# FrontendA.net
KiCad netlist of a schematic drawn in EAGLE
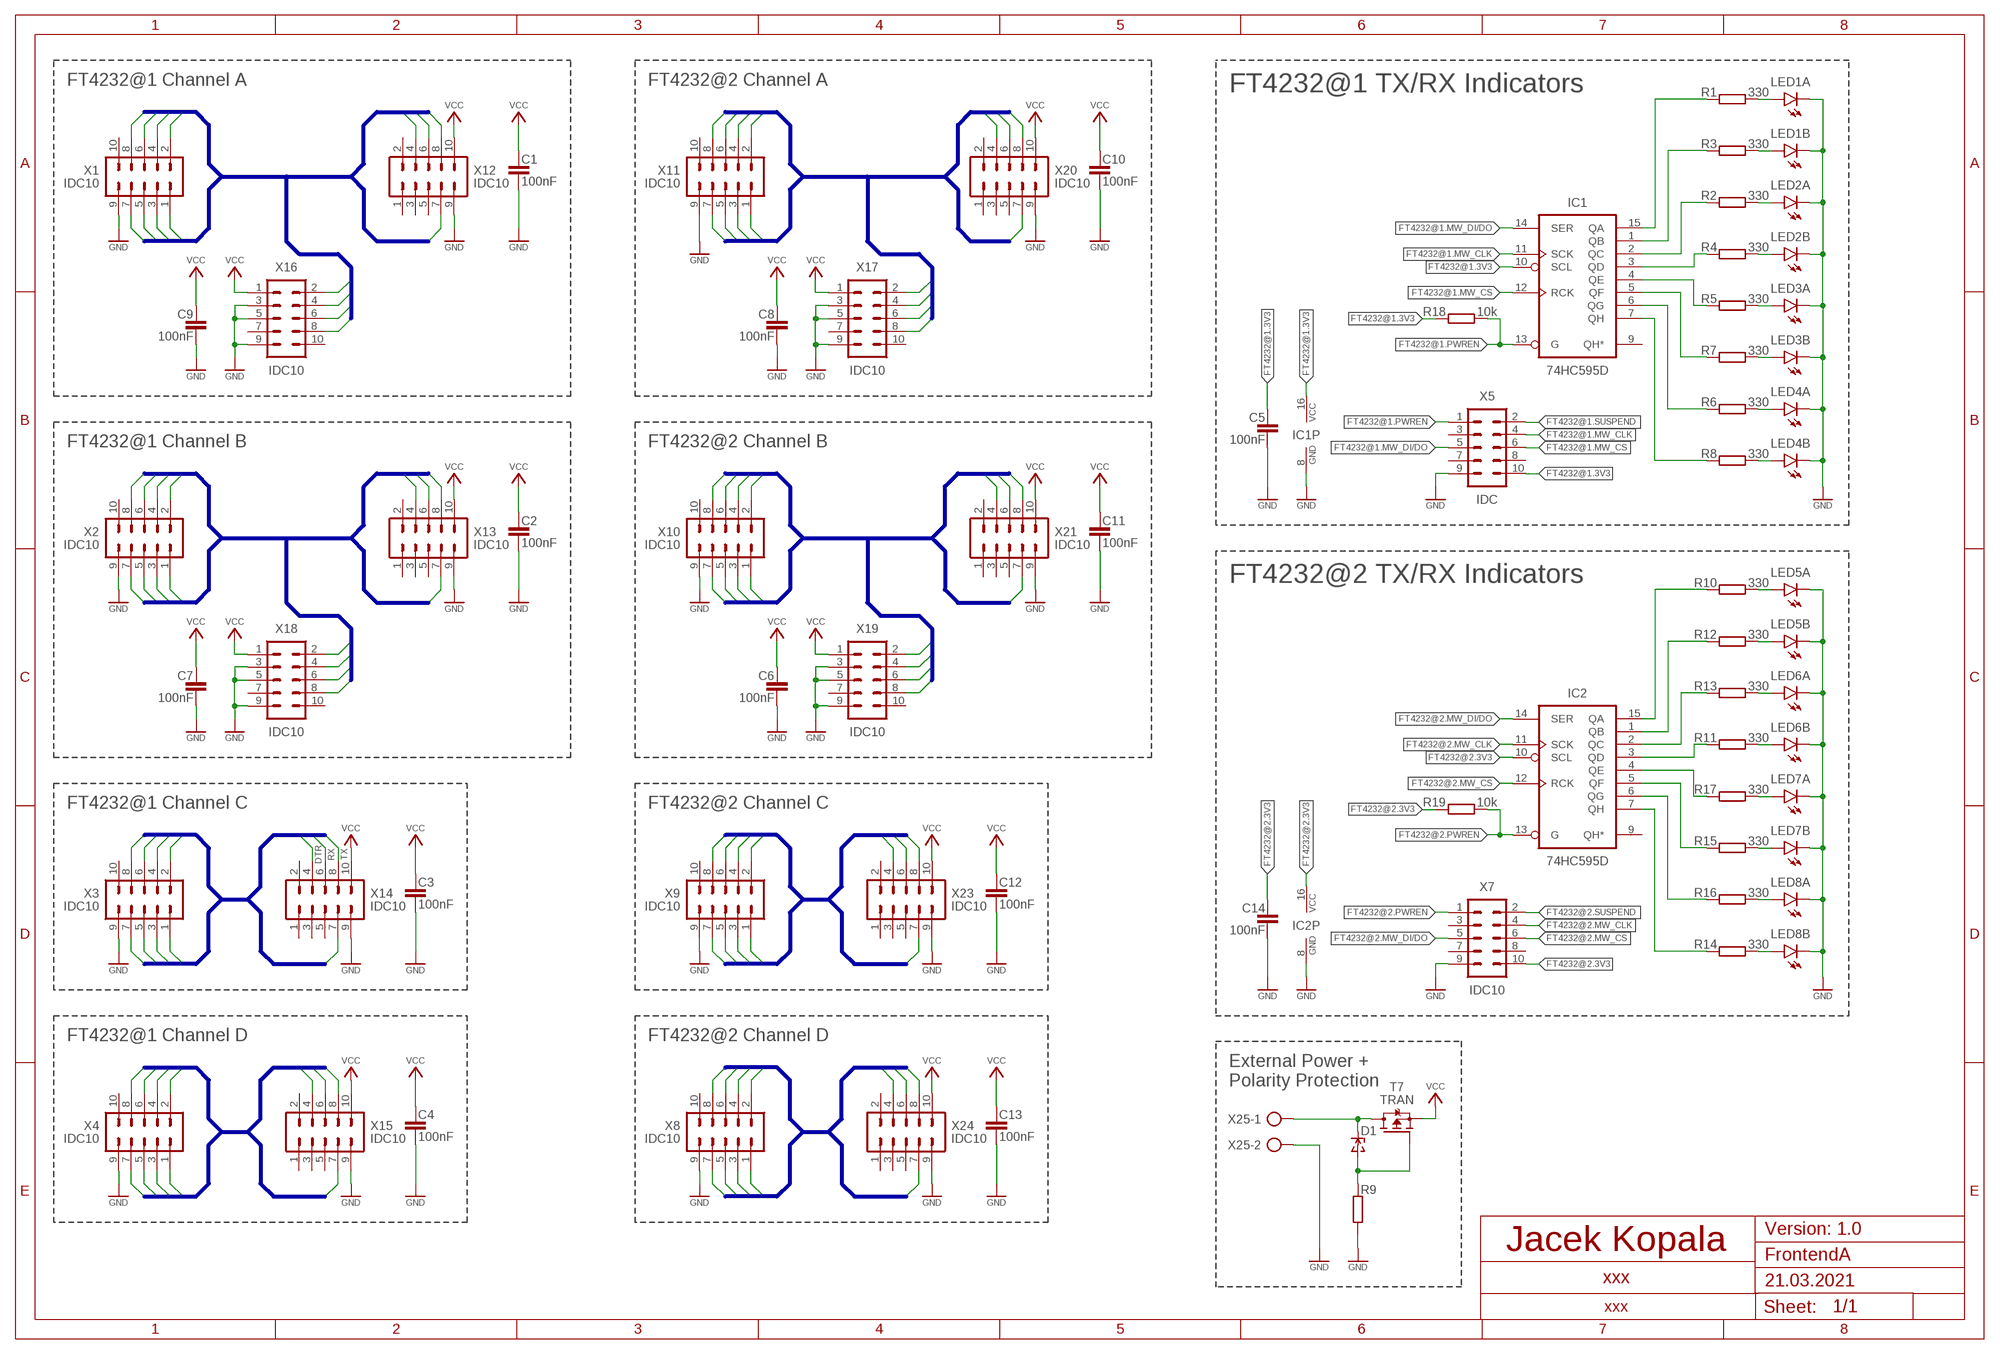
[diagram p0: schematic, sheet 1]

(export (version "E")
  (design (tool "Eeschema 10.0.6"))
  (components
    (comp (ref "C1")
      (value "100nF")
      (footprint "eagle-import:C0805")
      (libsource (lib "eagle-import") (part "C-EUC0805"))
    )
    (comp (ref "C2")
      (value "100nF")
      (footprint "eagle-import:C0805")
      (libsource (lib "eagle-import") (part "C-EUC0805"))
    )
    (comp (ref "C3")
      (value "100nF")
      (footprint "eagle-import:C0805")
      (libsource (lib "eagle-import") (part "C-EUC0805"))
    )
    (comp (ref "C4")
      (value "100nF")
      (footprint "eagle-import:C0805")
      (libsource (lib "eagle-import") (part "C-EUC0805"))
    )
    (comp (ref "C5")
      (value "100nF")
      (footprint "eagle-import:C0805")
      (libsource (lib "eagle-import") (part "C-EUC0805"))
    )
    (comp (ref "C6")
      (value "100nF")
      (footprint "eagle-import:C0805")
      (libsource (lib "eagle-import") (part "C-EUC0805"))
    )
    (comp (ref "C7")
      (value "100nF")
      (footprint "eagle-import:C0805")
      (libsource (lib "eagle-import") (part "C-EUC0805"))
    )
    (comp (ref "C8")
      (value "100nF")
      (footprint "eagle-import:C0805")
      (libsource (lib "eagle-import") (part "C-EUC0805"))
    )
    (comp (ref "C9")
      (value "100nF")
      (footprint "eagle-import:C0805")
      (libsource (lib "eagle-import") (part "C-EUC0805"))
    )
    (comp (ref "C10")
      (value "100nF")
      (footprint "eagle-import:C0805")
      (libsource (lib "eagle-import") (part "C-EUC0805"))
    )
    (comp (ref "C11")
      (value "100nF")
      (footprint "eagle-import:C0805")
      (libsource (lib "eagle-import") (part "C-EUC0805"))
    )
    (comp (ref "C12")
      (value "100nF")
      (footprint "eagle-import:C0805")
      (libsource (lib "eagle-import") (part "C-EUC0805"))
    )
    (comp (ref "C13")
      (value "100nF")
      (footprint "eagle-import:C0805")
      (libsource (lib "eagle-import") (part "C-EUC0805"))
    )
    (comp (ref "C14")
      (value "100nF")
      (footprint "eagle-import:C0805")
      (libsource (lib "eagle-import") (part "C-EUC0805"))
    )
    (comp (ref "D1")
      (value "ZENERSOD-323F")
      (footprint "eagle-import:SOD-323F")
      (libsource (lib "eagle-import") (part "ZENERSOD-323F"))
    )
    (comp (ref "IC1")
      (value "74HC595D")
      (footprint "eagle-import:SO16")
      (libsource (lib "eagle-import") (part "74595DHC"))
    )
    (comp (ref "IC2")
      (value "74HC595D")
      (footprint "eagle-import:SO16")
      (libsource (lib "eagle-import") (part "74595DHC"))
    )
    (comp (ref "LED1")
      (value "LSG-T676")
      (footprint "eagle-import:WL-SFCW-0603")
      (libsource (lib "eagle-import") (part "LSG-T676"))
    )
    (comp (ref "LED2")
      (value "LSG-T676")
      (footprint "eagle-import:WL-SFCW-0603")
      (libsource (lib "eagle-import") (part "LSG-T676"))
    )
    (comp (ref "LED3")
      (value "LSG-T676")
      (footprint "eagle-import:WL-SFCW-0603")
      (libsource (lib "eagle-import") (part "LSG-T676"))
    )
    (comp (ref "LED4")
      (value "LSG-T676")
      (footprint "eagle-import:WL-SFCW-0603")
      (libsource (lib "eagle-import") (part "LSG-T676"))
    )
    (comp (ref "LED5")
      (value "LSG-T676")
      (footprint "eagle-import:WL-SFCW-0603")
      (libsource (lib "eagle-import") (part "LSG-T676"))
    )
    (comp (ref "LED6")
      (value "LSG-T676")
      (footprint "eagle-import:WL-SFCW-0603")
      (libsource (lib "eagle-import") (part "LSG-T676"))
    )
    (comp (ref "LED7")
      (value "LSG-T676")
      (footprint "eagle-import:WL-SFCW-0603")
      (libsource (lib "eagle-import") (part "LSG-T676"))
    )
    (comp (ref "LED8")
      (value "LSG-T676")
      (footprint "eagle-import:WL-SFCW-0603")
      (libsource (lib "eagle-import") (part "LSG-T676"))
    )
    (comp (ref "R1")
      (value "330")
      (footprint "eagle-import:R0805")
      (libsource (lib "eagle-import") (part "R-EU_R0805"))
    )
    (comp (ref "R2")
      (value "330")
      (footprint "eagle-import:R0805")
      (libsource (lib "eagle-import") (part "R-EU_R0805"))
    )
    (comp (ref "R3")
      (value "330")
      (footprint "eagle-import:R0805")
      (libsource (lib "eagle-import") (part "R-EU_R0805"))
    )
    (comp (ref "R4")
      (value "330")
      (footprint "eagle-import:R0805")
      (libsource (lib "eagle-import") (part "R-EU_R0805"))
    )
    (comp (ref "R5")
      (value "330")
      (footprint "eagle-import:R0805")
      (libsource (lib "eagle-import") (part "R-EU_R0805"))
    )
    (comp (ref "R6")
      (value "330")
      (footprint "eagle-import:R0805")
      (libsource (lib "eagle-import") (part "R-EU_R0805"))
    )
    (comp (ref "R7")
      (value "330")
      (footprint "eagle-import:R0805")
      (libsource (lib "eagle-import") (part "R-EU_R0805"))
    )
    (comp (ref "R8")
      (value "330")
      (footprint "eagle-import:R0805")
      (libsource (lib "eagle-import") (part "R-EU_R0805"))
    )
    (comp (ref "R9")
      (value "R-EU_R0805")
      (footprint "eagle-import:R0805")
      (libsource (lib "eagle-import") (part "R-EU_R0805"))
    )
    (comp (ref "R10")
      (value "330")
      (footprint "eagle-import:R0805")
      (libsource (lib "eagle-import") (part "R-EU_R0805"))
    )
    (comp (ref "R11")
      (value "330")
      (footprint "eagle-import:R0805")
      (libsource (lib "eagle-import") (part "R-EU_R0805"))
    )
    (comp (ref "R12")
      (value "330")
      (footprint "eagle-import:R0805")
      (libsource (lib "eagle-import") (part "R-EU_R0805"))
    )
    (comp (ref "R13")
      (value "330")
      (footprint "eagle-import:R0805")
      (libsource (lib "eagle-import") (part "R-EU_R0805"))
    )
    (comp (ref "R14")
      (value "330")
      (footprint "eagle-import:R0805")
      (libsource (lib "eagle-import") (part "R-EU_R0805"))
    )
    (comp (ref "R15")
      (value "330")
      (footprint "eagle-import:R0805")
      (libsource (lib "eagle-import") (part "R-EU_R0805"))
    )
    (comp (ref "R16")
      (value "330")
      (footprint "eagle-import:R0805")
      (libsource (lib "eagle-import") (part "R-EU_R0805"))
    )
    (comp (ref "R17")
      (value "330")
      (footprint "eagle-import:R0805")
      (libsource (lib "eagle-import") (part "R-EU_R0805"))
    )
    (comp (ref "R18")
      (value "10k")
      (footprint "eagle-import:R0805")
      (libsource (lib "eagle-import") (part "R-EU_R0805"))
    )
    (comp (ref "R19")
      (value "10k")
      (footprint "eagle-import:R0805")
      (libsource (lib "eagle-import") (part "R-EU_R0805"))
    )
    (comp (ref "T7")
      (value "TRAN")
      (footprint "eagle-import:TO252")
      (libsource (lib "eagle-import") (part "FDD4141TO252"))
    )
    (comp (ref "X1")
      (value "IDC10")
      (footprint "eagle-import:MA05-2")
      (libsource (lib "eagle-import") (part "MA05-2"))
    )
    (comp (ref "X2")
      (value "IDC10")
      (footprint "eagle-import:MA05-2")
      (libsource (lib "eagle-import") (part "MA05-2"))
    )
    (comp (ref "X3")
      (value "IDC10")
      (footprint "eagle-import:MA05-2")
      (libsource (lib "eagle-import") (part "MA05-2"))
    )
    (comp (ref "X4")
      (value "IDC10")
      (footprint "eagle-import:MA05-2")
      (libsource (lib "eagle-import") (part "MA05-2"))
    )
    (comp (ref "X5")
      (value "IDC")
      (footprint "eagle-import:MA05-2")
      (libsource (lib "eagle-import") (part "MA05-2"))
    )
    (comp (ref "X7")
      (value "IDC10")
      (footprint "eagle-import:MA05-2")
      (libsource (lib "eagle-import") (part "MA05-2"))
    )
    (comp (ref "X8")
      (value "IDC10")
      (footprint "eagle-import:MA05-2")
      (libsource (lib "eagle-import") (part "MA05-2"))
    )
    (comp (ref "X9")
      (value "IDC10")
      (footprint "eagle-import:MA05-2")
      (libsource (lib "eagle-import") (part "MA05-2"))
    )
    (comp (ref "X10")
      (value "IDC10")
      (footprint "eagle-import:MA05-2")
      (libsource (lib "eagle-import") (part "MA05-2"))
    )
    (comp (ref "X11")
      (value "IDC10")
      (footprint "eagle-import:MA05-2")
      (libsource (lib "eagle-import") (part "MA05-2"))
    )
    (comp (ref "X12")
      (value "IDC10")
      (footprint "eagle-import:ML10")
      (libsource (lib "eagle-import") (part "ML10"))
    )
    (comp (ref "X13")
      (value "IDC10")
      (footprint "eagle-import:ML10")
      (libsource (lib "eagle-import") (part "ML10"))
    )
    (comp (ref "X14")
      (value "IDC10")
      (footprint "eagle-import:ML10")
      (libsource (lib "eagle-import") (part "ML10"))
    )
    (comp (ref "X15")
      (value "IDC10")
      (footprint "eagle-import:ML10")
      (libsource (lib "eagle-import") (part "ML10"))
    )
    (comp (ref "X16")
      (value "IDC10")
      (footprint "eagle-import:ML10")
      (libsource (lib "eagle-import") (part "ML10"))
    )
    (comp (ref "X17")
      (value "IDC10")
      (footprint "eagle-import:ML10")
      (libsource (lib "eagle-import") (part "ML10"))
    )
    (comp (ref "X18")
      (value "IDC10")
      (footprint "eagle-import:ML10")
      (libsource (lib "eagle-import") (part "ML10"))
    )
    (comp (ref "X19")
      (value "IDC10")
      (footprint "eagle-import:ML10")
      (libsource (lib "eagle-import") (part "ML10"))
    )
    (comp (ref "X20")
      (value "IDC10")
      (footprint "eagle-import:ML10")
      (libsource (lib "eagle-import") (part "ML10"))
    )
    (comp (ref "X21")
      (value "IDC10")
      (footprint "eagle-import:ML10")
      (libsource (lib "eagle-import") (part "ML10"))
    )
    (comp (ref "X23")
      (value "IDC10")
      (footprint "eagle-import:ML10")
      (libsource (lib "eagle-import") (part "ML10"))
    )
    (comp (ref "X24")
      (value "IDC10")
      (footprint "eagle-import:ML10")
      (libsource (lib "eagle-import") (part "ML10"))
    )
    (comp (ref "X25")
      (value "AK500/2")
      (footprint "eagle-import:AK500_2")
      (libsource (lib "eagle-import") (part "AK500/2"))
    )
  )
  (nets
    (net (code "1") (name "/FT4232@1.AD0") (class "Default")
      (node (ref "X1") (pin "1") (pinfunction "1_1") (pintype "passive"))
      (node (ref "X12") (pin "8") (pinfunction "8_8") (pintype "passive"))
      (node (ref "X16") (pin "4") (pinfunction "4_4") (pintype "passive"))
    )
    (net (code "2") (name "/FT4232@1.AD1") (class "Default")
      (node (ref "X1") (pin "2") (pinfunction "2_2") (pintype "passive"))
      (node (ref "X12") (pin "6") (pinfunction "6_6") (pintype "passive"))
      (node (ref "X16") (pin "8") (pinfunction "8_8") (pintype "passive"))
    )
    (net (code "3") (name "/FT4232@1.AD2") (class "Default")
      (node (ref "X1") (pin "3") (pinfunction "3_3") (pintype "passive"))
      (node (ref "X12") (pin "7") (pinfunction "7_7") (pintype "passive"))
      (node (ref "X16") (pin "6") (pinfunction "6_6") (pintype "passive"))
    )
    (net (code "4") (name "/FT4232@1.AD3") (class "Default")
      (node (ref "X1") (pin "4") (pinfunction "4_4") (pintype "passive"))
      (node (ref "X16") (pin "2") (pinfunction "2_2") (pintype "passive"))
    )
    (net (code "5") (name "/FT4232@1.AD4") (class "Default")
      (node (ref "X1") (pin "5") (pinfunction "5_5") (pintype "passive"))
      (node (ref "X12") (pin "4") (pinfunction "4_4") (pintype "passive"))
    )
    (net (code "6") (name "/FT4232@1.BD0") (class "Default")
      (node (ref "X13") (pin "8") (pinfunction "8_8") (pintype "passive"))
      (node (ref "X18") (pin "4") (pinfunction "4_4") (pintype "passive"))
      (node (ref "X2") (pin "1") (pinfunction "1_1") (pintype "passive"))
    )
    (net (code "7") (name "/FT4232@1.BD1") (class "Default")
      (node (ref "X13") (pin "6") (pinfunction "6_6") (pintype "passive"))
      (node (ref "X18") (pin "8") (pinfunction "8_8") (pintype "passive"))
      (node (ref "X2") (pin "2") (pinfunction "2_2") (pintype "passive"))
    )
    (net (code "8") (name "/FT4232@1.BD2") (class "Default")
      (node (ref "X13") (pin "7") (pinfunction "7_7") (pintype "passive"))
      (node (ref "X18") (pin "6") (pinfunction "6_6") (pintype "passive"))
      (node (ref "X2") (pin "3") (pinfunction "3_3") (pintype "passive"))
    )
    (net (code "9") (name "/FT4232@1.BD3") (class "Default")
      (node (ref "X18") (pin "2") (pinfunction "2_2") (pintype "passive"))
      (node (ref "X2") (pin "4") (pinfunction "4_4") (pintype "passive"))
    )
    (net (code "10") (name "/FT4232@1.BD4") (class "Default")
      (node (ref "X13") (pin "4") (pinfunction "4_4") (pintype "passive"))
      (node (ref "X2") (pin "5") (pinfunction "5_5") (pintype "passive"))
    )
    (net (code "11") (name "/FT4232@1.CD0") (class "Default")
      (node (ref "X14") (pin "8") (pinfunction "8_8") (pintype "passive"))
      (node (ref "X3") (pin "1") (pinfunction "1_1") (pintype "passive"))
    )
    (net (code "12") (name "/FT4232@1.CD1") (class "Default")
      (node (ref "X14") (pin "6") (pinfunction "6_6") (pintype "passive"))
      (node (ref "X3") (pin "2") (pinfunction "2_2") (pintype "passive"))
    )
    (net (code "13") (name "/FT4232@1.CD2") (class "Default")
      (node (ref "X14") (pin "7") (pinfunction "7_7") (pintype "passive"))
      (node (ref "X3") (pin "3") (pinfunction "3_3") (pintype "passive"))
    )
    (net (code "14") (name "/FT4232@1.CD4") (class "Default")
      (node (ref "X14") (pin "4") (pinfunction "4_4") (pintype "passive"))
      (node (ref "X3") (pin "5") (pinfunction "5_5") (pintype "passive"))
    )
    (net (code "15") (name "/FT4232@1.DD0") (class "Default")
      (node (ref "X15") (pin "8") (pinfunction "8_8") (pintype "passive"))
      (node (ref "X4") (pin "1") (pinfunction "1_1") (pintype "passive"))
    )
    (net (code "16") (name "/FT4232@1.DD1") (class "Default")
      (node (ref "X15") (pin "6") (pinfunction "6_6") (pintype "passive"))
      (node (ref "X4") (pin "2") (pinfunction "2_2") (pintype "passive"))
    )
    (net (code "17") (name "/FT4232@1.DD2") (class "Default")
      (node (ref "X15") (pin "7") (pinfunction "7_7") (pintype "passive"))
      (node (ref "X4") (pin "3") (pinfunction "3_3") (pintype "passive"))
    )
    (net (code "18") (name "/FT4232@1.DD4") (class "Default")
      (node (ref "X15") (pin "4") (pinfunction "4_4") (pintype "passive"))
      (node (ref "X4") (pin "5") (pinfunction "5_5") (pintype "passive"))
    )
    (net (code "19") (name "/FT4232@2.AD0") (class "Default")
      (node (ref "X11") (pin "1") (pinfunction "1_1") (pintype "passive"))
      (node (ref "X17") (pin "4") (pinfunction "4_4") (pintype "passive"))
      (node (ref "X20") (pin "8") (pinfunction "8_8") (pintype "passive"))
    )
    (net (code "20") (name "/FT4232@2.AD1") (class "Default")
      (node (ref "X11") (pin "2") (pinfunction "2_2") (pintype "passive"))
      (node (ref "X17") (pin "8") (pinfunction "8_8") (pintype "passive"))
      (node (ref "X20") (pin "6") (pinfunction "6_6") (pintype "passive"))
    )
    (net (code "21") (name "/FT4232@2.AD2") (class "Default")
      (node (ref "X11") (pin "3") (pinfunction "3_3") (pintype "passive"))
      (node (ref "X17") (pin "6") (pinfunction "6_6") (pintype "passive"))
      (node (ref "X20") (pin "7") (pinfunction "7_7") (pintype "passive"))
    )
    (net (code "22") (name "/FT4232@2.AD3") (class "Default")
      (node (ref "X11") (pin "4") (pinfunction "4_4") (pintype "passive"))
      (node (ref "X17") (pin "2") (pinfunction "2_2") (pintype "passive"))
    )
    (net (code "23") (name "/FT4232@2.AD4") (class "Default")
      (node (ref "X11") (pin "5") (pinfunction "5_5") (pintype "passive"))
      (node (ref "X20") (pin "4") (pinfunction "4_4") (pintype "passive"))
    )
    (net (code "24") (name "/FT4232@2.BD0") (class "Default")
      (node (ref "X10") (pin "1") (pinfunction "1_1") (pintype "passive"))
      (node (ref "X19") (pin "4") (pinfunction "4_4") (pintype "passive"))
      (node (ref "X21") (pin "8") (pinfunction "8_8") (pintype "passive"))
    )
    (net (code "25") (name "/FT4232@2.BD1") (class "Default")
      (node (ref "X10") (pin "2") (pinfunction "2_2") (pintype "passive"))
      (node (ref "X19") (pin "8") (pinfunction "8_8") (pintype "passive"))
      (node (ref "X21") (pin "6") (pinfunction "6_6") (pintype "passive"))
    )
    (net (code "26") (name "/FT4232@2.BD2") (class "Default")
      (node (ref "X10") (pin "3") (pinfunction "3_3") (pintype "passive"))
      (node (ref "X19") (pin "6") (pinfunction "6_6") (pintype "passive"))
      (node (ref "X21") (pin "7") (pinfunction "7_7") (pintype "passive"))
    )
    (net (code "27") (name "/FT4232@2.BD3") (class "Default")
      (node (ref "X10") (pin "4") (pinfunction "4_4") (pintype "passive"))
      (node (ref "X19") (pin "2") (pinfunction "2_2") (pintype "passive"))
    )
    (net (code "28") (name "/FT4232@2.BD4") (class "Default")
      (node (ref "X10") (pin "5") (pinfunction "5_5") (pintype "passive"))
      (node (ref "X21") (pin "4") (pinfunction "4_4") (pintype "passive"))
    )
    (net (code "29") (name "/FT4232@2.CD0") (class "Default")
      (node (ref "X23") (pin "8") (pinfunction "8_8") (pintype "passive"))
      (node (ref "X9") (pin "1") (pinfunction "1_1") (pintype "passive"))
    )
    (net (code "30") (name "/FT4232@2.CD1") (class "Default")
      (node (ref "X23") (pin "6") (pinfunction "6_6") (pintype "passive"))
      (node (ref "X9") (pin "2") (pinfunction "2_2") (pintype "passive"))
    )
    (net (code "31") (name "/FT4232@2.CD2") (class "Default")
      (node (ref "X23") (pin "7") (pinfunction "7_7") (pintype "passive"))
      (node (ref "X9") (pin "3") (pinfunction "3_3") (pintype "passive"))
    )
    (net (code "32") (name "/FT4232@2.CD4") (class "Default")
      (node (ref "X23") (pin "4") (pinfunction "4_4") (pintype "passive"))
      (node (ref "X9") (pin "5") (pinfunction "5_5") (pintype "passive"))
    )
    (net (code "33") (name "/FT4232@2.DD0") (class "Default")
      (node (ref "X24") (pin "8") (pinfunction "8_8") (pintype "passive"))
      (node (ref "X8") (pin "1") (pinfunction "1_1") (pintype "passive"))
    )
    (net (code "34") (name "/FT4232@2.DD1") (class "Default")
      (node (ref "X24") (pin "6") (pinfunction "6_6") (pintype "passive"))
      (node (ref "X8") (pin "2") (pinfunction "2_2") (pintype "passive"))
    )
    (net (code "35") (name "/FT4232@2.DD2") (class "Default")
      (node (ref "X24") (pin "7") (pinfunction "7_7") (pintype "passive"))
      (node (ref "X8") (pin "3") (pinfunction "3_3") (pintype "passive"))
    )
    (net (code "36") (name "/FT4232@2.DD4") (class "Default")
      (node (ref "X24") (pin "4") (pinfunction "4_4") (pintype "passive"))
      (node (ref "X8") (pin "5") (pinfunction "5_5") (pintype "passive"))
    )
    (net (code "37") (name "FT4232@1.3V3") (class "Default")
      (node (ref "C5") (pin "1") (pinfunction "1_1") (pintype "passive"))
      (node (ref "IC1") (pin "10") (pinfunction "SCL_10") (pintype "input"))
      (node (ref "IC1") (pin "16") (pinfunction "VCC_16") (pintype "power_in"))
      (node (ref "R18") (pin "2") (pinfunction "2_2") (pintype "passive"))
      (node (ref "X5") (pin "10") (pinfunction "10_10") (pintype "passive"))
    )
    (net (code "38") (name "FT4232@1.MW_CLK") (class "Default")
      (node (ref "IC1") (pin "11") (pinfunction "SCK_11") (pintype "input"))
      (node (ref "X5") (pin "4") (pinfunction "4_4") (pintype "passive"))
    )
    (net (code "39") (name "FT4232@1.MW_CS") (class "Default")
      (node (ref "IC1") (pin "12") (pinfunction "RCK_12") (pintype "input"))
      (node (ref "X5") (pin "6") (pinfunction "6_6") (pintype "passive"))
    )
    (net (code "40") (name "FT4232@1.MW_DI{slash}DO") (class "Default")
      (node (ref "IC1") (pin "14") (pinfunction "SER_14") (pintype "input"))
      (node (ref "X5") (pin "5") (pinfunction "5_5") (pintype "passive"))
    )
    (net (code "41") (name "FT4232@1.PWREN") (class "Default")
      (node (ref "IC1") (pin "13") (pinfunction "G_13") (pintype "input"))
      (node (ref "R18") (pin "1") (pinfunction "1_1") (pintype "passive"))
      (node (ref "X5") (pin "1") (pinfunction "1_1") (pintype "passive"))
    )
    (net (code "42") (name "FT4232@1.SUSPEND") (class "Default")
      (node (ref "X5") (pin "2") (pinfunction "2_2") (pintype "passive"))
    )
    (net (code "43") (name "FT4232@2.3V3") (class "Default")
      (node (ref "C14") (pin "1") (pinfunction "1_1") (pintype "passive"))
      (node (ref "IC2") (pin "10") (pinfunction "SCL_10") (pintype "input"))
      (node (ref "IC2") (pin "16") (pinfunction "VCC_16") (pintype "power_in"))
      (node (ref "R19") (pin "2") (pinfunction "2_2") (pintype "passive"))
      (node (ref "X7") (pin "10") (pinfunction "10_10") (pintype "passive"))
    )
    (net (code "44") (name "FT4232@2.MW_CLK") (class "Default")
      (node (ref "IC2") (pin "11") (pinfunction "SCK_11") (pintype "input"))
      (node (ref "X7") (pin "4") (pinfunction "4_4") (pintype "passive"))
    )
    (net (code "45") (name "FT4232@2.MW_CS") (class "Default")
      (node (ref "IC2") (pin "12") (pinfunction "RCK_12") (pintype "input"))
      (node (ref "X7") (pin "6") (pinfunction "6_6") (pintype "passive"))
    )
    (net (code "46") (name "FT4232@2.MW_DI{slash}DO") (class "Default")
      (node (ref "IC2") (pin "14") (pinfunction "SER_14") (pintype "input"))
      (node (ref "X7") (pin "5") (pinfunction "5_5") (pintype "passive"))
    )
    (net (code "47") (name "FT4232@2.PWREN") (class "Default")
      (node (ref "IC2") (pin "13") (pinfunction "G_13") (pintype "input"))
      (node (ref "R19") (pin "1") (pinfunction "1_1") (pintype "passive"))
      (node (ref "X7") (pin "1") (pinfunction "1_1") (pintype "passive"))
    )
    (net (code "48") (name "FT4232@2.SUSPEND") (class "Default")
      (node (ref "X7") (pin "2") (pinfunction "2_2") (pintype "passive"))
    )
    (net (code "49") (name "GND") (class "Default")
      (node (ref "C1") (pin "2") (pinfunction "2_2") (pintype "passive"))
      (node (ref "C10") (pin "2") (pinfunction "2_2") (pintype "passive"))
      (node (ref "C11") (pin "2") (pinfunction "2_2") (pintype "passive"))
      (node (ref "C12") (pin "2") (pinfunction "2_2") (pintype "passive"))
      (node (ref "C13") (pin "2") (pinfunction "2_2") (pintype "passive"))
      (node (ref "C14") (pin "2") (pinfunction "2_2") (pintype "passive"))
      (node (ref "C2") (pin "2") (pinfunction "2_2") (pintype "passive"))
      (node (ref "C3") (pin "2") (pinfunction "2_2") (pintype "passive"))
      (node (ref "C4") (pin "2") (pinfunction "2_2") (pintype "passive"))
      (node (ref "C5") (pin "2") (pinfunction "2_2") (pintype "passive"))
      (node (ref "C6") (pin "2") (pinfunction "2_2") (pintype "passive"))
      (node (ref "C7") (pin "2") (pinfunction "2_2") (pintype "passive"))
      (node (ref "C8") (pin "2") (pinfunction "2_2") (pintype "passive"))
      (node (ref "C9") (pin "2") (pinfunction "2_2") (pintype "passive"))
      (node (ref "IC1") (pin "8") (pinfunction "GND_8") (pintype "power_in"))
      (node (ref "IC2") (pin "8") (pinfunction "GND_8") (pintype "power_in"))
      (node (ref "LED1") (pin "P$1") (pinfunction "C_P$1") (pintype "passive"))
      (node (ref "LED1") (pin "P$3") (pinfunction "C_P$3") (pintype "passive"))
      (node (ref "LED2") (pin "P$1") (pinfunction "C_P$1") (pintype "passive"))
      (node (ref "LED2") (pin "P$3") (pinfunction "C_P$3") (pintype "passive"))
      (node (ref "LED3") (pin "P$1") (pinfunction "C_P$1") (pintype "passive"))
      (node (ref "LED3") (pin "P$3") (pinfunction "C_P$3") (pintype "passive"))
      (node (ref "LED4") (pin "P$1") (pinfunction "C_P$1") (pintype "passive"))
      (node (ref "LED4") (pin "P$3") (pinfunction "C_P$3") (pintype "passive"))
      (node (ref "LED5") (pin "P$1") (pinfunction "C_P$1") (pintype "passive"))
      (node (ref "LED5") (pin "P$3") (pinfunction "C_P$3") (pintype "passive"))
      (node (ref "LED6") (pin "P$1") (pinfunction "C_P$1") (pintype "passive"))
      (node (ref "LED6") (pin "P$3") (pinfunction "C_P$3") (pintype "passive"))
      (node (ref "LED7") (pin "P$1") (pinfunction "C_P$1") (pintype "passive"))
      (node (ref "LED7") (pin "P$3") (pinfunction "C_P$3") (pintype "passive"))
      (node (ref "LED8") (pin "P$1") (pinfunction "C_P$1") (pintype "passive"))
      (node (ref "LED8") (pin "P$3") (pinfunction "C_P$3") (pintype "passive"))
      (node (ref "R9") (pin "1") (pinfunction "1_1") (pintype "passive"))
      (node (ref "X1") (pin "9") (pinfunction "9_9") (pintype "passive"))
      (node (ref "X10") (pin "9") (pinfunction "9_9") (pintype "passive"))
      (node (ref "X11") (pin "9") (pinfunction "9_9") (pintype "passive"))
      (node (ref "X12") (pin "9") (pinfunction "9_9") (pintype "passive"))
      (node (ref "X13") (pin "9") (pinfunction "9_9") (pintype "passive"))
      (node (ref "X14") (pin "9") (pinfunction "9_9") (pintype "passive"))
      (node (ref "X15") (pin "9") (pinfunction "9_9") (pintype "passive"))
      (node (ref "X16") (pin "3") (pinfunction "3_3") (pintype "passive"))
      (node (ref "X16") (pin "5") (pinfunction "5_5") (pintype "passive"))
      (node (ref "X16") (pin "9") (pinfunction "9_9") (pintype "passive"))
      (node (ref "X17") (pin "3") (pinfunction "3_3") (pintype "passive"))
      (node (ref "X17") (pin "5") (pinfunction "5_5") (pintype "passive"))
      (node (ref "X17") (pin "9") (pinfunction "9_9") (pintype "passive"))
      (node (ref "X18") (pin "3") (pinfunction "3_3") (pintype "passive"))
      (node (ref "X18") (pin "5") (pinfunction "5_5") (pintype "passive"))
      (node (ref "X18") (pin "9") (pinfunction "9_9") (pintype "passive"))
      (node (ref "X19") (pin "3") (pinfunction "3_3") (pintype "passive"))
      (node (ref "X19") (pin "5") (pinfunction "5_5") (pintype "passive"))
      (node (ref "X19") (pin "9") (pinfunction "9_9") (pintype "passive"))
      (node (ref "X2") (pin "9") (pinfunction "9_9") (pintype "passive"))
      (node (ref "X20") (pin "9") (pinfunction "9_9") (pintype "passive"))
      (node (ref "X21") (pin "9") (pinfunction "9_9") (pintype "passive"))
      (node (ref "X23") (pin "9") (pinfunction "9_9") (pintype "passive"))
      (node (ref "X24") (pin "9") (pinfunction "9_9") (pintype "passive"))
      (node (ref "X25") (pin "2") (pinfunction "KL_2") (pintype "passive"))
      (node (ref "X3") (pin "9") (pinfunction "9_9") (pintype "passive"))
      (node (ref "X4") (pin "9") (pinfunction "9_9") (pintype "passive"))
      (node (ref "X5") (pin "9") (pinfunction "9_9") (pintype "passive"))
      (node (ref "X7") (pin "9") (pinfunction "9_9") (pintype "passive"))
      (node (ref "X8") (pin "9") (pinfunction "9_9") (pintype "passive"))
      (node (ref "X9") (pin "9") (pinfunction "9_9") (pintype "passive"))
    )
    (net (code "50") (name "Net-(IC1A-QA)") (class "Default")
      (node (ref "IC1") (pin "15") (pinfunction "QA_15") (pintype "tri_state"))
      (node (ref "R1") (pin "1") (pinfunction "1_1") (pintype "passive"))
    )
    (net (code "51") (name "Net-(IC1A-QB)") (class "Default")
      (node (ref "IC1") (pin "1") (pinfunction "QB_1") (pintype "tri_state"))
      (node (ref "R3") (pin "1") (pinfunction "1_1") (pintype "passive"))
    )
    (net (code "52") (name "Net-(IC1A-QC)") (class "Default")
      (node (ref "IC1") (pin "2") (pinfunction "QC_2") (pintype "tri_state"))
      (node (ref "R2") (pin "1") (pinfunction "1_1") (pintype "passive"))
    )
    (net (code "53") (name "Net-(IC1A-QD)") (class "Default")
      (node (ref "IC1") (pin "3") (pinfunction "QD_3") (pintype "tri_state"))
      (node (ref "R4") (pin "1") (pinfunction "1_1") (pintype "passive"))
    )
    (net (code "54") (name "Net-(IC1A-QE)") (class "Default")
      (node (ref "IC1") (pin "4") (pinfunction "QE_4") (pintype "tri_state"))
      (node (ref "R5") (pin "1") (pinfunction "1_1") (pintype "passive"))
    )
    (net (code "55") (name "Net-(IC1A-QF)") (class "Default")
      (node (ref "IC1") (pin "5") (pinfunction "QF_5") (pintype "tri_state"))
      (node (ref "R7") (pin "1") (pinfunction "1_1") (pintype "passive"))
    )
    (net (code "56") (name "Net-(IC1A-QG)") (class "Default")
      (node (ref "IC1") (pin "6") (pinfunction "QG_6") (pintype "tri_state"))
      (node (ref "R6") (pin "1") (pinfunction "1_1") (pintype "passive"))
    )
    (net (code "57") (name "Net-(IC1A-QH)") (class "Default")
      (node (ref "IC1") (pin "7") (pinfunction "QH_7") (pintype "tri_state"))
      (node (ref "R8") (pin "1") (pinfunction "1_1") (pintype "passive"))
    )
    (net (code "58") (name "Net-(IC2A-QA)") (class "Default")
      (node (ref "IC2") (pin "15") (pinfunction "QA_15") (pintype "tri_state"))
      (node (ref "R10") (pin "1") (pinfunction "1_1") (pintype "passive"))
    )
    (net (code "59") (name "Net-(IC2A-QB)") (class "Default")
      (node (ref "IC2") (pin "1") (pinfunction "QB_1") (pintype "tri_state"))
      (node (ref "R12") (pin "1") (pinfunction "1_1") (pintype "passive"))
    )
    (net (code "60") (name "Net-(IC2A-QC)") (class "Default")
      (node (ref "IC2") (pin "2") (pinfunction "QC_2") (pintype "tri_state"))
      (node (ref "R13") (pin "1") (pinfunction "1_1") (pintype "passive"))
    )
    (net (code "61") (name "Net-(IC2A-QD)") (class "Default")
      (node (ref "IC2") (pin "3") (pinfunction "QD_3") (pintype "tri_state"))
      (node (ref "R11") (pin "1") (pinfunction "1_1") (pintype "passive"))
    )
    (net (code "62") (name "Net-(IC2A-QE)") (class "Default")
      (node (ref "IC2") (pin "4") (pinfunction "QE_4") (pintype "tri_state"))
      (node (ref "R17") (pin "1") (pinfunction "1_1") (pintype "passive"))
    )
    (net (code "63") (name "Net-(IC2A-QF)") (class "Default")
      (node (ref "IC2") (pin "5") (pinfunction "QF_5") (pintype "tri_state"))
      (node (ref "R15") (pin "1") (pinfunction "1_1") (pintype "passive"))
    )
    (net (code "64") (name "Net-(IC2A-QG)") (class "Default")
      (node (ref "IC2") (pin "6") (pinfunction "QG_6") (pintype "tri_state"))
      (node (ref "R16") (pin "1") (pinfunction "1_1") (pintype "passive"))
    )
    (net (code "65") (name "Net-(IC2A-QH)") (class "Default")
      (node (ref "IC2") (pin "7") (pinfunction "QH_7") (pintype "tri_state"))
      (node (ref "R14") (pin "1") (pinfunction "1_1") (pintype "passive"))
    )
    (net (code "66") (name "Net-(LED1A-A)") (class "Default")
      (node (ref "LED1") (pin "P$2") (pinfunction "A_P$2") (pintype "passive"))
      (node (ref "R1") (pin "2") (pinfunction "2_2") (pintype "passive"))
    )
    (net (code "67") (name "Net-(LED1B-A)") (class "Default")
      (node (ref "LED1") (pin "P$4") (pinfunction "A_P$4") (pintype "passive"))
      (node (ref "R3") (pin "2") (pinfunction "2_2") (pintype "passive"))
    )
    (net (code "68") (name "Net-(LED2A-A)") (class "Default")
      (node (ref "LED2") (pin "P$2") (pinfunction "A_P$2") (pintype "passive"))
      (node (ref "R2") (pin "2") (pinfunction "2_2") (pintype "passive"))
    )
    (net (code "69") (name "Net-(LED2B-A)") (class "Default")
      (node (ref "LED2") (pin "P$4") (pinfunction "A_P$4") (pintype "passive"))
      (node (ref "R4") (pin "2") (pinfunction "2_2") (pintype "passive"))
    )
    (net (code "70") (name "Net-(LED3A-A)") (class "Default")
      (node (ref "LED3") (pin "P$2") (pinfunction "A_P$2") (pintype "passive"))
      (node (ref "R5") (pin "2") (pinfunction "2_2") (pintype "passive"))
    )
    (net (code "71") (name "Net-(LED3B-A)") (class "Default")
      (node (ref "LED3") (pin "P$4") (pinfunction "A_P$4") (pintype "passive"))
      (node (ref "R7") (pin "2") (pinfunction "2_2") (pintype "passive"))
    )
    (net (code "72") (name "Net-(LED4A-A)") (class "Default")
      (node (ref "LED4") (pin "P$2") (pinfunction "A_P$2") (pintype "passive"))
      (node (ref "R6") (pin "2") (pinfunction "2_2") (pintype "passive"))
    )
    (net (code "73") (name "Net-(LED4B-A)") (class "Default")
      (node (ref "LED4") (pin "P$4") (pinfunction "A_P$4") (pintype "passive"))
      (node (ref "R8") (pin "2") (pinfunction "2_2") (pintype "passive"))
    )
    (net (code "74") (name "Net-(LED5A-A)") (class "Default")
      (node (ref "LED5") (pin "P$2") (pinfunction "A_P$2") (pintype "passive"))
      (node (ref "R10") (pin "2") (pinfunction "2_2") (pintype "passive"))
    )
    (net (code "75") (name "Net-(LED5B-A)") (class "Default")
      (node (ref "LED5") (pin "P$4") (pinfunction "A_P$4") (pintype "passive"))
      (node (ref "R12") (pin "2") (pinfunction "2_2") (pintype "passive"))
    )
    (net (code "76") (name "Net-(LED6A-A)") (class "Default")
      (node (ref "LED6") (pin "P$2") (pinfunction "A_P$2") (pintype "passive"))
      (node (ref "R13") (pin "2") (pinfunction "2_2") (pintype "passive"))
    )
    (net (code "77") (name "Net-(LED6B-A)") (class "Default")
      (node (ref "LED6") (pin "P$4") (pinfunction "A_P$4") (pintype "passive"))
      (node (ref "R11") (pin "2") (pinfunction "2_2") (pintype "passive"))
    )
    (net (code "78") (name "Net-(LED7A-A)") (class "Default")
      (node (ref "LED7") (pin "P$2") (pinfunction "A_P$2") (pintype "passive"))
      (node (ref "R17") (pin "2") (pinfunction "2_2") (pintype "passive"))
    )
    (net (code "79") (name "Net-(LED7B-A)") (class "Default")
      (node (ref "LED7") (pin "P$4") (pinfunction "A_P$4") (pintype "passive"))
      (node (ref "R15") (pin "2") (pinfunction "2_2") (pintype "passive"))
    )
    (net (code "80") (name "Net-(LED8A-A)") (class "Default")
      (node (ref "LED8") (pin "P$2") (pinfunction "A_P$2") (pintype "passive"))
      (node (ref "R16") (pin "2") (pinfunction "2_2") (pintype "passive"))
    )
    (net (code "81") (name "Net-(LED8B-A)") (class "Default")
      (node (ref "LED8") (pin "P$4") (pinfunction "A_P$4") (pintype "passive"))
      (node (ref "R14") (pin "2") (pinfunction "2_2") (pintype "passive"))
    )
    (net (code "82") (name "Net-(T7-D)") (class "Default")
      (node (ref "D1") (pin "C") (pinfunction "C_C") (pintype "passive"))
      (node (ref "T7") (pin "3") (pinfunction "D_3") (pintype "passive"))
      (node (ref "X25") (pin "1") (pinfunction "KL_1") (pintype "passive"))
    )
    (net (code "83") (name "Net-(T7-G)") (class "Default")
      (node (ref "D1") (pin "A") (pinfunction "A_A") (pintype "passive"))
      (node (ref "R9") (pin "2") (pinfunction "2_2") (pintype "passive"))
      (node (ref "T7") (pin "1") (pinfunction "G_1") (pintype "passive"))
    )
    (net (code "84") (name "VCC") (class "Default")
      (node (ref "C1") (pin "1") (pinfunction "1_1") (pintype "passive"))
      (node (ref "C10") (pin "1") (pinfunction "1_1") (pintype "passive"))
      (node (ref "C11") (pin "1") (pinfunction "1_1") (pintype "passive"))
      (node (ref "C12") (pin "1") (pinfunction "1_1") (pintype "passive"))
      (node (ref "C13") (pin "1") (pinfunction "1_1") (pintype "passive"))
      (node (ref "C2") (pin "1") (pinfunction "1_1") (pintype "passive"))
      (node (ref "C3") (pin "1") (pinfunction "1_1") (pintype "passive"))
      (node (ref "C4") (pin "1") (pinfunction "1_1") (pintype "passive"))
      (node (ref "C6") (pin "1") (pinfunction "1_1") (pintype "passive"))
      (node (ref "C7") (pin "1") (pinfunction "1_1") (pintype "passive"))
      (node (ref "C8") (pin "1") (pinfunction "1_1") (pintype "passive"))
      (node (ref "C9") (pin "1") (pinfunction "1_1") (pintype "passive"))
      (node (ref "T7") (pin "2") (pinfunction "S_2") (pintype "passive"))
      (node (ref "X12") (pin "10") (pinfunction "10_10") (pintype "passive"))
      (node (ref "X13") (pin "10") (pinfunction "10_10") (pintype "passive"))
      (node (ref "X14") (pin "10") (pinfunction "10_10") (pintype "passive"))
      (node (ref "X15") (pin "10") (pinfunction "10_10") (pintype "passive"))
      (node (ref "X16") (pin "1") (pinfunction "1_1") (pintype "passive"))
      (node (ref "X17") (pin "1") (pinfunction "1_1") (pintype "passive"))
      (node (ref "X18") (pin "1") (pinfunction "1_1") (pintype "passive"))
      (node (ref "X19") (pin "1") (pinfunction "1_1") (pintype "passive"))
      (node (ref "X20") (pin "10") (pinfunction "10_10") (pintype "passive"))
      (node (ref "X21") (pin "10") (pinfunction "10_10") (pintype "passive"))
      (node (ref "X23") (pin "10") (pinfunction "10_10") (pintype "passive"))
      (node (ref "X24") (pin "10") (pinfunction "10_10") (pintype "passive"))
    )
    (net (code "85") (name "unconnected-(IC1A-QH*-Pad9)") (class "Default")
      (node (ref "IC1") (pin "9") (pinfunction "QH*_9") (pintype "tri_state"))
    )
    (net (code "86") (name "unconnected-(IC2A-QH*-Pad9)") (class "Default")
      (node (ref "IC2") (pin "9") (pinfunction "QH*_9") (pintype "tri_state"))
    )
    (net (code "87") (name "unconnected-(X1-Pad6)") (class "Default")
      (node (ref "X1") (pin "6") (pinfunction "6_6") (pintype "passive"))
    )
    (net (code "88") (name "unconnected-(X1-Pad7)") (class "Default")
      (node (ref "X1") (pin "7") (pinfunction "7_7") (pintype "passive"))
    )
    (net (code "89") (name "unconnected-(X1-Pad8)") (class "Default")
      (node (ref "X1") (pin "8") (pinfunction "8_8") (pintype "passive"))
    )
    (net (code "90") (name "unconnected-(X1-Pad10)") (class "Default")
      (node (ref "X1") (pin "10") (pinfunction "10_10") (pintype "passive"))
    )
    (net (code "91") (name "unconnected-(X2-Pad6)") (class "Default")
      (node (ref "X2") (pin "6") (pinfunction "6_6") (pintype "passive"))
    )
    (net (code "92") (name "unconnected-(X2-Pad7)") (class "Default")
      (node (ref "X2") (pin "7") (pinfunction "7_7") (pintype "passive"))
    )
    (net (code "93") (name "unconnected-(X2-Pad8)") (class "Default")
      (node (ref "X2") (pin "8") (pinfunction "8_8") (pintype "passive"))
    )
    (net (code "94") (name "unconnected-(X2-Pad10)") (class "Default")
      (node (ref "X2") (pin "10") (pinfunction "10_10") (pintype "passive"))
    )
    (net (code "95") (name "unconnected-(X3-Pad4)") (class "Default")
      (node (ref "X3") (pin "4") (pinfunction "4_4") (pintype "passive"))
    )
    (net (code "96") (name "unconnected-(X3-Pad6)") (class "Default")
      (node (ref "X3") (pin "6") (pinfunction "6_6") (pintype "passive"))
    )
    (net (code "97") (name "unconnected-(X3-Pad7)") (class "Default")
      (node (ref "X3") (pin "7") (pinfunction "7_7") (pintype "passive"))
    )
    (net (code "98") (name "unconnected-(X3-Pad8)") (class "Default")
      (node (ref "X3") (pin "8") (pinfunction "8_8") (pintype "passive"))
    )
    (net (code "99") (name "unconnected-(X3-Pad10)") (class "Default")
      (node (ref "X3") (pin "10") (pinfunction "10_10") (pintype "passive"))
    )
    (net (code "100") (name "unconnected-(X4-Pad4)") (class "Default")
      (node (ref "X4") (pin "4") (pinfunction "4_4") (pintype "passive"))
    )
    (net (code "101") (name "unconnected-(X4-Pad6)") (class "Default")
      (node (ref "X4") (pin "6") (pinfunction "6_6") (pintype "passive"))
    )
    (net (code "102") (name "unconnected-(X4-Pad7)") (class "Default")
      (node (ref "X4") (pin "7") (pinfunction "7_7") (pintype "passive"))
    )
    (net (code "103") (name "unconnected-(X4-Pad8)") (class "Default")
      (node (ref "X4") (pin "8") (pinfunction "8_8") (pintype "passive"))
    )
    (net (code "104") (name "unconnected-(X4-Pad10)") (class "Default")
      (node (ref "X4") (pin "10") (pinfunction "10_10") (pintype "passive"))
    )
    (net (code "105") (name "unconnected-(X5-Pad3)") (class "Default")
      (node (ref "X5") (pin "3") (pinfunction "3_3") (pintype "passive"))
    )
    (net (code "106") (name "unconnected-(X5-Pad7)") (class "Default")
      (node (ref "X5") (pin "7") (pinfunction "7_7") (pintype "passive"))
    )
    (net (code "107") (name "unconnected-(X5-Pad8)") (class "Default")
      (node (ref "X5") (pin "8") (pinfunction "8_8") (pintype "passive"))
    )
    (net (code "108") (name "unconnected-(X7-Pad3)") (class "Default")
      (node (ref "X7") (pin "3") (pinfunction "3_3") (pintype "passive"))
    )
    (net (code "109") (name "unconnected-(X7-Pad7)") (class "Default")
      (node (ref "X7") (pin "7") (pinfunction "7_7") (pintype "passive"))
    )
    (net (code "110") (name "unconnected-(X7-Pad8)") (class "Default")
      (node (ref "X7") (pin "8") (pinfunction "8_8") (pintype "passive"))
    )
    (net (code "111") (name "unconnected-(X8-Pad4)") (class "Default")
      (node (ref "X8") (pin "4") (pinfunction "4_4") (pintype "passive"))
    )
    (net (code "112") (name "unconnected-(X8-Pad6)") (class "Default")
      (node (ref "X8") (pin "6") (pinfunction "6_6") (pintype "passive"))
    )
    (net (code "113") (name "unconnected-(X8-Pad7)") (class "Default")
      (node (ref "X8") (pin "7") (pinfunction "7_7") (pintype "passive"))
    )
    (net (code "114") (name "unconnected-(X8-Pad8)") (class "Default")
      (node (ref "X8") (pin "8") (pinfunction "8_8") (pintype "passive"))
    )
    (net (code "115") (name "unconnected-(X8-Pad10)") (class "Default")
      (node (ref "X8") (pin "10") (pinfunction "10_10") (pintype "passive"))
    )
    (net (code "116") (name "unconnected-(X9-Pad4)") (class "Default")
      (node (ref "X9") (pin "4") (pinfunction "4_4") (pintype "passive"))
    )
    (net (code "117") (name "unconnected-(X9-Pad6)") (class "Default")
      (node (ref "X9") (pin "6") (pinfunction "6_6") (pintype "passive"))
    )
    (net (code "118") (name "unconnected-(X9-Pad7)") (class "Default")
      (node (ref "X9") (pin "7") (pinfunction "7_7") (pintype "passive"))
    )
    (net (code "119") (name "unconnected-(X9-Pad8)") (class "Default")
      (node (ref "X9") (pin "8") (pinfunction "8_8") (pintype "passive"))
    )
    (net (code "120") (name "unconnected-(X9-Pad10)") (class "Default")
      (node (ref "X9") (pin "10") (pinfunction "10_10") (pintype "passive"))
    )
    (net (code "121") (name "unconnected-(X10-Pad6)") (class "Default")
      (node (ref "X10") (pin "6") (pinfunction "6_6") (pintype "passive"))
    )
    (net (code "122") (name "unconnected-(X10-Pad7)") (class "Default")
      (node (ref "X10") (pin "7") (pinfunction "7_7") (pintype "passive"))
    )
    (net (code "123") (name "unconnected-(X10-Pad8)") (class "Default")
      (node (ref "X10") (pin "8") (pinfunction "8_8") (pintype "passive"))
    )
    (net (code "124") (name "unconnected-(X10-Pad10)") (class "Default")
      (node (ref "X10") (pin "10") (pinfunction "10_10") (pintype "passive"))
    )
    (net (code "125") (name "unconnected-(X11-Pad6)") (class "Default")
      (node (ref "X11") (pin "6") (pinfunction "6_6") (pintype "passive"))
    )
    (net (code "126") (name "unconnected-(X11-Pad7)") (class "Default")
      (node (ref "X11") (pin "7") (pinfunction "7_7") (pintype "passive"))
    )
    (net (code "127") (name "unconnected-(X11-Pad8)") (class "Default")
      (node (ref "X11") (pin "8") (pinfunction "8_8") (pintype "passive"))
    )
    (net (code "128") (name "unconnected-(X11-Pad10)") (class "Default")
      (node (ref "X11") (pin "10") (pinfunction "10_10") (pintype "passive"))
    )
    (net (code "129") (name "unconnected-(X12-Pad1)") (class "Default")
      (node (ref "X12") (pin "1") (pinfunction "1_1") (pintype "passive"))
    )
    (net (code "130") (name "unconnected-(X12-Pad2)") (class "Default")
      (node (ref "X12") (pin "2") (pinfunction "2_2") (pintype "passive"))
    )
    (net (code "131") (name "unconnected-(X12-Pad3)") (class "Default")
      (node (ref "X12") (pin "3") (pinfunction "3_3") (pintype "passive"))
    )
    (net (code "132") (name "unconnected-(X12-Pad5)") (class "Default")
      (node (ref "X12") (pin "5") (pinfunction "5_5") (pintype "passive"))
    )
    (net (code "133") (name "unconnected-(X13-Pad1)") (class "Default")
      (node (ref "X13") (pin "1") (pinfunction "1_1") (pintype "passive"))
    )
    (net (code "134") (name "unconnected-(X13-Pad2)") (class "Default")
      (node (ref "X13") (pin "2") (pinfunction "2_2") (pintype "passive"))
    )
    (net (code "135") (name "unconnected-(X13-Pad3)") (class "Default")
      (node (ref "X13") (pin "3") (pinfunction "3_3") (pintype "passive"))
    )
    (net (code "136") (name "unconnected-(X13-Pad5)") (class "Default")
      (node (ref "X13") (pin "5") (pinfunction "5_5") (pintype "passive"))
    )
    (net (code "137") (name "unconnected-(X14-Pad1)") (class "Default")
      (node (ref "X14") (pin "1") (pinfunction "1_1") (pintype "passive"))
    )
    (net (code "138") (name "unconnected-(X14-Pad2)") (class "Default")
      (node (ref "X14") (pin "2") (pinfunction "2_2") (pintype "passive"))
    )
    (net (code "139") (name "unconnected-(X14-Pad3)") (class "Default")
      (node (ref "X14") (pin "3") (pinfunction "3_3") (pintype "passive"))
    )
    (net (code "140") (name "unconnected-(X14-Pad5)") (class "Default")
      (node (ref "X14") (pin "5") (pinfunction "5_5") (pintype "passive"))
    )
    (net (code "141") (name "unconnected-(X15-Pad1)") (class "Default")
      (node (ref "X15") (pin "1") (pinfunction "1_1") (pintype "passive"))
    )
    (net (code "142") (name "unconnected-(X15-Pad2)") (class "Default")
      (node (ref "X15") (pin "2") (pinfunction "2_2") (pintype "passive"))
    )
    (net (code "143") (name "unconnected-(X15-Pad3)") (class "Default")
      (node (ref "X15") (pin "3") (pinfunction "3_3") (pintype "passive"))
    )
    (net (code "144") (name "unconnected-(X15-Pad5)") (class "Default")
      (node (ref "X15") (pin "5") (pinfunction "5_5") (pintype "passive"))
    )
    (net (code "145") (name "unconnected-(X16-Pad7)") (class "Default")
      (node (ref "X16") (pin "7") (pinfunction "7_7") (pintype "passive"))
    )
    (net (code "146") (name "unconnected-(X16-Pad10)") (class "Default")
      (node (ref "X16") (pin "10") (pinfunction "10_10") (pintype "passive"))
    )
    (net (code "147") (name "unconnected-(X17-Pad7)") (class "Default")
      (node (ref "X17") (pin "7") (pinfunction "7_7") (pintype "passive"))
    )
    (net (code "148") (name "unconnected-(X17-Pad10)") (class "Default")
      (node (ref "X17") (pin "10") (pinfunction "10_10") (pintype "passive"))
    )
    (net (code "149") (name "unconnected-(X18-Pad7)") (class "Default")
      (node (ref "X18") (pin "7") (pinfunction "7_7") (pintype "passive"))
    )
    (net (code "150") (name "unconnected-(X18-Pad10)") (class "Default")
      (node (ref "X18") (pin "10") (pinfunction "10_10") (pintype "passive"))
    )
    (net (code "151") (name "unconnected-(X19-Pad7)") (class "Default")
      (node (ref "X19") (pin "7") (pinfunction "7_7") (pintype "passive"))
    )
    (net (code "152") (name "unconnected-(X19-Pad10)") (class "Default")
      (node (ref "X19") (pin "10") (pinfunction "10_10") (pintype "passive"))
    )
    (net (code "153") (name "unconnected-(X20-Pad1)") (class "Default")
      (node (ref "X20") (pin "1") (pinfunction "1_1") (pintype "passive"))
    )
    (net (code "154") (name "unconnected-(X20-Pad2)") (class "Default")
      (node (ref "X20") (pin "2") (pinfunction "2_2") (pintype "passive"))
    )
    (net (code "155") (name "unconnected-(X20-Pad3)") (class "Default")
      (node (ref "X20") (pin "3") (pinfunction "3_3") (pintype "passive"))
    )
    (net (code "156") (name "unconnected-(X20-Pad5)") (class "Default")
      (node (ref "X20") (pin "5") (pinfunction "5_5") (pintype "passive"))
    )
    (net (code "157") (name "unconnected-(X21-Pad1)") (class "Default")
      (node (ref "X21") (pin "1") (pinfunction "1_1") (pintype "passive"))
    )
    (net (code "158") (name "unconnected-(X21-Pad2)") (class "Default")
      (node (ref "X21") (pin "2") (pinfunction "2_2") (pintype "passive"))
    )
    (net (code "159") (name "unconnected-(X21-Pad3)") (class "Default")
      (node (ref "X21") (pin "3") (pinfunction "3_3") (pintype "passive"))
    )
    (net (code "160") (name "unconnected-(X21-Pad5)") (class "Default")
      (node (ref "X21") (pin "5") (pinfunction "5_5") (pintype "passive"))
    )
    (net (code "161") (name "unconnected-(X23-Pad1)") (class "Default")
      (node (ref "X23") (pin "1") (pinfunction "1_1") (pintype "passive"))
    )
    (net (code "162") (name "unconnected-(X23-Pad2)") (class "Default")
      (node (ref "X23") (pin "2") (pinfunction "2_2") (pintype "passive"))
    )
    (net (code "163") (name "unconnected-(X23-Pad3)") (class "Default")
      (node (ref "X23") (pin "3") (pinfunction "3_3") (pintype "passive"))
    )
    (net (code "164") (name "unconnected-(X23-Pad5)") (class "Default")
      (node (ref "X23") (pin "5") (pinfunction "5_5") (pintype "passive"))
    )
    (net (code "165") (name "unconnected-(X24-Pad1)") (class "Default")
      (node (ref "X24") (pin "1") (pinfunction "1_1") (pintype "passive"))
    )
    (net (code "166") (name "unconnected-(X24-Pad2)") (class "Default")
      (node (ref "X24") (pin "2") (pinfunction "2_2") (pintype "passive"))
    )
    (net (code "167") (name "unconnected-(X24-Pad3)") (class "Default")
      (node (ref "X24") (pin "3") (pinfunction "3_3") (pintype "passive"))
    )
    (net (code "168") (name "unconnected-(X24-Pad5)") (class "Default")
      (node (ref "X24") (pin "5") (pinfunction "5_5") (pintype "passive"))
    )
  )
)
